# alim_MOSFET_1.net
KiCad netlist of a schematic drawn in Altium Designer
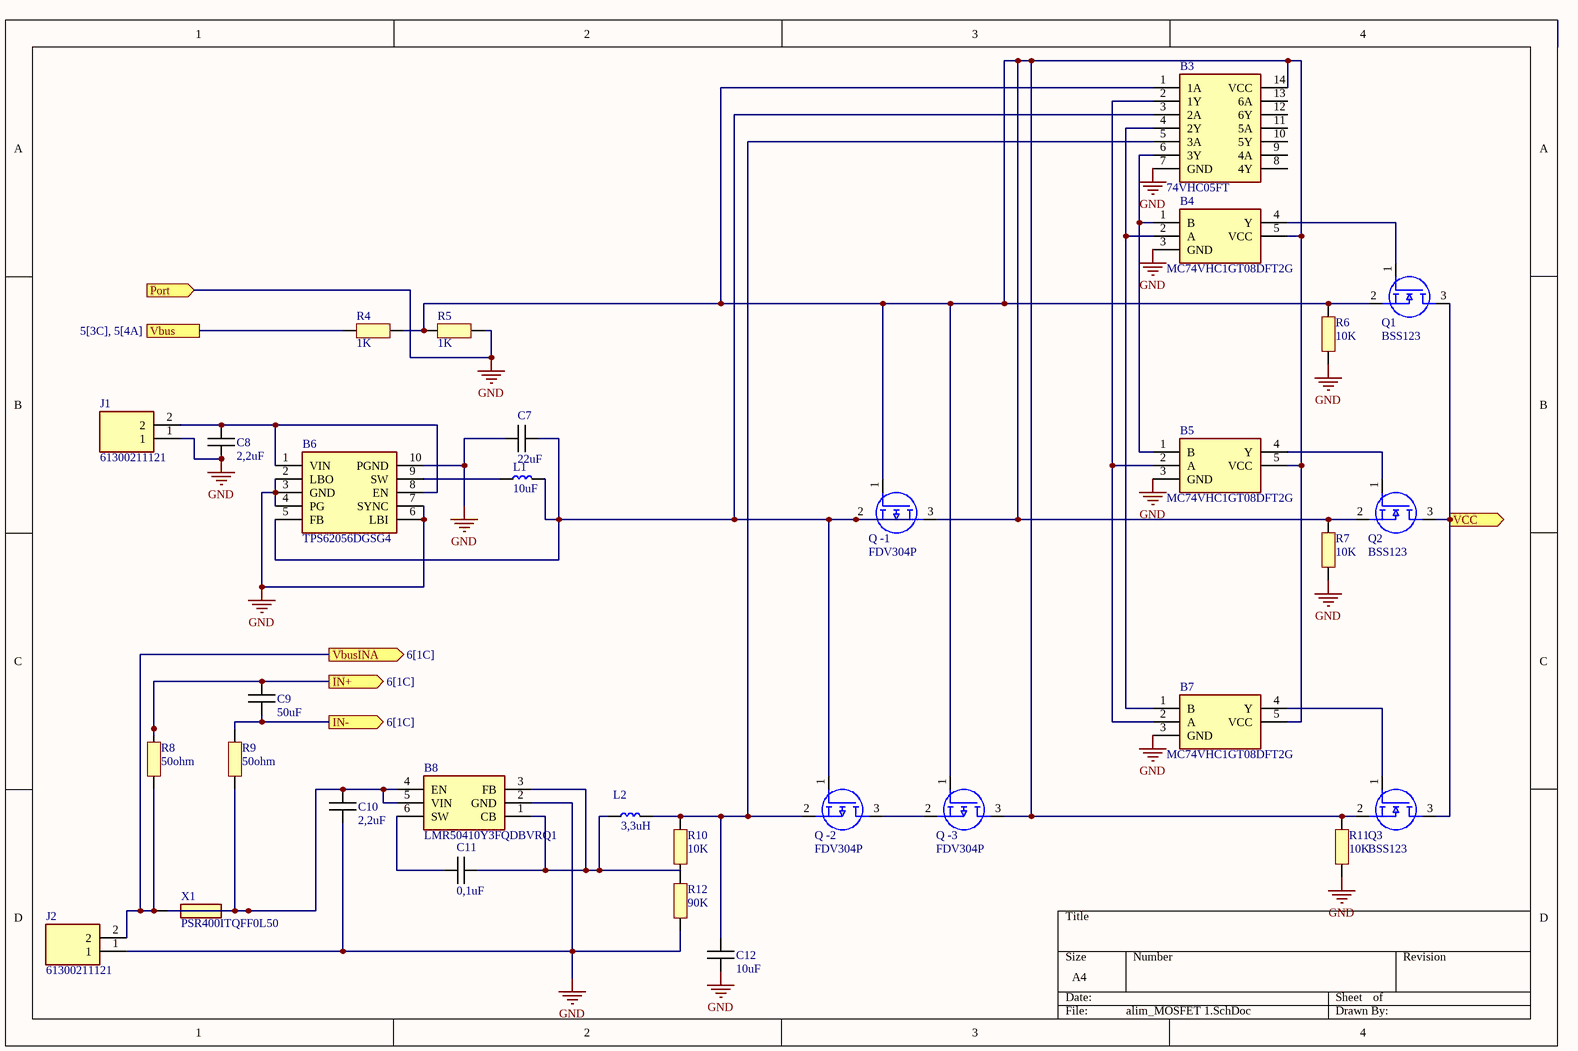
[diagram p0: alim_MOSFET 1.SchDoc]

(export (version "E")
  (design (tool "Eeschema 10.0.6"))
  (components
    (comp (ref "B3")
      (value "74VHC05FT")
      (footprint "SOP65P640X120-14N")
      (description "Logic Gates CMOS LOGIC IC INVERTER")
      (fields (field (name "MOUSER PART NUMBER") "757-74VHC05FT"))
      (libsource (lib "SCHLibrary") (part "74VHC05FT"))
    )
    (comp (ref "B4")
      (value "MC74VHC1GT08DFT2G")
      (footprint "SOT65P210X110-5N")
      (description "Single 2-Input AND Gate, TTL Level")
      (libsource (lib "SCHLibrary") (part "MC74VHC1GT08DFT2G"))
    )
    (comp (ref "B5")
      (value "MC74VHC1GT08DFT2G")
      (footprint "SOT65P210X110-5N")
      (description "Single 2-Input AND Gate, TTL Level")
      (libsource (lib "SCHLibrary") (part "MC74VHC1GT08DFT2G"))
    )
    (comp (ref "B6")
      (value "TPS62056DGSG4")
      (footprint "SOP50P490X110-10N")
      (fields (field (name "MOUSER PART NUMBER") "595-TPS62056DGSG4"))
      (libsource (lib "SCHLibrary") (part "TPS62056DGSG4"))
    )
    (comp (ref "B7")
      (value "MC74VHC1GT08DFT2G")
      (footprint "SOT65P210X110-5N")
      (description "Single 2-Input AND Gate, TTL Level")
      (libsource (lib "SCHLibrary") (part "MC74VHC1GT08DFT2G"))
    )
    (comp (ref "B8")
      (value "LMR50410Y3FQDBVRQ1")
      (footprint "SOT95P280X145-6N")
      (fields (field (name "MOUSER PART NUMBER") "595-R50410Y3FQDBVRQ1"))
      (libsource (lib "SCHLibrary") (part "LMR50410Y3FQDBVRQ1"))
    )
    (comp (ref "C7")
      (value "22uF")
      (footprint "CAPC1005X06N")
      (libsource (lib "SCHLibrary") (part "Capacitor"))
    )
    (comp (ref "C8")
      (value "2,2uF")
      (footprint "CAPC1005X06N")
      (libsource (lib "SCHLibrary") (part "Capacitor"))
    )
    (comp (ref "C9")
      (value "50uF")
      (footprint "CAPC1005X06N")
      (libsource (lib "SCHLibrary") (part "Capacitor"))
    )
    (comp (ref "C10")
      (value "2,2uF")
      (footprint "CAPC1005X06N")
      (libsource (lib "SCHLibrary") (part "Capacitor"))
    )
    (comp (ref "C11")
      (value "0,1uF")
      (footprint "CAPC1005X06N")
      (libsource (lib "SCHLibrary") (part "Capacitor"))
    )
    (comp (ref "C12")
      (value "10uF")
      (footprint "CAPC1005X06N")
      (libsource (lib "SCHLibrary") (part "Capacitor"))
    )
    (comp (ref "J1")
      (value "61300211121")
      (footprint "61300211121")
      (description "WURTH ELEKTRONIK - 61300211121 - HEADER, 2.54MM, PIN, THT, VERTICAL, 2WAY")
      (libsource (lib "SCHLibrary") (part "61300211121"))
    )
    (comp (ref "J2")
      (value "61300211121")
      (footprint "61300211121")
      (description "WURTH ELEKTRONIK - 61300211121 - HEADER, 2.54MM, PIN, THT, VERTICAL, 2WAY")
      (libsource (lib "SCHLibrary") (part "61300211121"))
    )
    (comp (ref "L1") (value "10uF") (footprint "LQPC1005X06N") (libsource (lib "SCHLibrary") (part "Bobine")))
    (comp (ref "L2")
      (value "3,3uH")
      (footprint "LQPC1005X06N")
      (libsource (lib "SCHLibrary") (part "Bobine"))
    )
    (comp (ref "Q -1")
      (value "FDV304P")
      (footprint "SOT95P251X112-3N")
      (fields (field (name "MOUSER PART NUMBER") "512-FDV304P"))
      (libsource (lib "SCHLibrary") (part "FDV304P"))
    )
    (comp (ref "Q -2")
      (value "FDV304P")
      (footprint "SOT95P251X112-3N")
      (fields (field (name "MOUSER PART NUMBER") "512-FDV304P"))
      (libsource (lib "SCHLibrary") (part "FDV304P"))
    )
    (comp (ref "Q -3")
      (value "FDV304P")
      (footprint "SOT95P251X112-3N")
      (fields (field (name "MOUSER PART NUMBER") "512-FDV304P"))
      (libsource (lib "SCHLibrary") (part "FDV304P"))
    )
    (comp (ref "Q1")
      (value "BSS123")
      (footprint "BSS123")
      (description "BSS123 N-Channel MOSFET, 170 mA, 100 V PowerTrench, 3-Pin SOT-23 ON Semiconductor")
      (libsource (lib "SCHLibrary") (part "BSS123"))
    )
    (comp (ref "Q2")
      (value "BSS123")
      (footprint "BSS123")
      (description "BSS123 N-Channel MOSFET, 170 mA, 100 V PowerTrench, 3-Pin SOT-23 ON Semiconductor")
      (libsource (lib "SCHLibrary") (part "BSS123"))
    )
    (comp (ref "Q3")
      (value "BSS123")
      (footprint "BSS123")
      (description "BSS123 N-Channel MOSFET, 170 mA, 100 V PowerTrench, 3-Pin SOT-23 ON Semiconductor")
      (libsource (lib "SCHLibrary") (part "BSS123"))
    )
    (comp (ref "R4") (value "1K") (footprint "RESC1005X06N") (libsource (lib "") (part "Resistor_1")))
    (comp (ref "R5") (value "1K") (footprint "RESC1005X06N") (libsource (lib "") (part "Resistor_1")))
    (comp (ref "R6")
      (value "10K")
      (footprint "RESC1005X06N")
      (libsource (lib "SCHLibrary") (part "Resistor"))
    )
    (comp (ref "R7")
      (value "10K")
      (footprint "RESC1005X06N")
      (libsource (lib "SCHLibrary") (part "Resistor"))
    )
    (comp (ref "R8") (value "50ohm") (footprint "RESC1005X06N") (libsource (lib "") (part "Resistor_2")))
    (comp (ref "R9") (value "50ohm") (footprint "RESC1005X06N") (libsource (lib "") (part "Resistor_2")))
    (comp (ref "R10")
      (value "10K")
      (footprint "RESC1005X06N")
      (libsource (lib "SCHLibrary") (part "Resistor"))
    )
    (comp (ref "R11")
      (value "10K")
      (footprint "RESC1005X06N")
      (libsource (lib "SCHLibrary") (part "Resistor"))
    )
    (comp (ref "R12")
      (value "90K")
      (footprint "RESC1005X06N")
      (libsource (lib "SCHLibrary") (part "Resistor"))
    )
    (comp (ref "X1")
      (value "PSR400ITQFF0L50")
      (footprint "RESC10052X200N")
      (fields (field (name "MOUSER PART NUMBER") "755-PSR400ITQFF0L50"))
      (libsource (lib "SCHLibrary") (part "PSR400ITQFF0L50"))
    )
  )
  (nets
    (net (code "1") (name "/IN+") (class "Default")
      (node (ref "C9") (pin "1") (pinfunction "1_1") (pintype "passive"))
      (node (ref "R8") (pin "2") (pinfunction "2_2") (pintype "passive"))
    )
    (net (code "2") (name "/IN-") (class "Default")
      (node (ref "C9") (pin "2") (pinfunction "2_2") (pintype "passive"))
      (node (ref "R9") (pin "2") (pinfunction "2_2") (pintype "passive"))
    )
    (net (code "3") (name "/VCC") (class "Default")
      (node (ref "Q1") (pin "3") (pinfunction "D_3") (pintype "passive"))
      (node (ref "Q2") (pin "3") (pinfunction "D_3") (pintype "passive"))
      (node (ref "Q3") (pin "3") (pinfunction "D_3") (pintype "passive"))
    )
    (net (code "4") (name "/Vbus") (class "Default")
      (node (ref "R4") (pin "1") (pinfunction "1_1") (pintype "passive"))
    )
    (net (code "5") (name "/VbusINA") (class "Default")
      (node (ref "J2") (pin "2") (pinfunction "2_2") (pintype "passive"))
      (node (ref "R8") (pin "1") (pinfunction "1_1") (pintype "passive"))
      (node (ref "X1") (pin "1") (pinfunction "1_1") (pintype "passive"))
    )
    (net (code "6") (name "GND") (class "Default")
      (node (ref "B3") (pin "7") (pinfunction "GND_7") (pintype "passive"))
      (node (ref "B4") (pin "3") (pinfunction "GND_3") (pintype "passive"))
      (node (ref "B5") (pin "3") (pinfunction "GND_3") (pintype "passive"))
      (node (ref "B6") (pin "10") (pinfunction "PGND_10") (pintype "passive"))
      (node (ref "B6") (pin "2") (pinfunction "LBO_2") (pintype "passive"))
      (node (ref "B6") (pin "3") (pinfunction "GND_3") (pintype "passive"))
      (node (ref "B6") (pin "4") (pinfunction "PG_4") (pintype "passive"))
      (node (ref "B6") (pin "6") (pinfunction "LBI_6") (pintype "passive"))
      (node (ref "B6") (pin "7") (pinfunction "SYNC_7") (pintype "passive"))
      (node (ref "B7") (pin "3") (pinfunction "GND_3") (pintype "passive"))
      (node (ref "B8") (pin "2") (pinfunction "GND_2") (pintype "passive"))
      (node (ref "C10") (pin "2") (pinfunction "2_2") (pintype "passive"))
      (node (ref "C12") (pin "2") (pinfunction "2_2") (pintype "passive"))
      (node (ref "C7") (pin "2") (pinfunction "2_2") (pintype "passive"))
      (node (ref "C8") (pin "2") (pinfunction "2_2") (pintype "passive"))
      (node (ref "J1") (pin "1") (pinfunction "1_1") (pintype "passive"))
      (node (ref "J2") (pin "1") (pinfunction "1_1") (pintype "passive"))
      (node (ref "R11") (pin "2") (pinfunction "2_2") (pintype "passive"))
      (node (ref "R12") (pin "2") (pinfunction "2_2") (pintype "passive"))
      (node (ref "R5") (pin "2") (pinfunction "2_2") (pintype "passive"))
      (node (ref "R6") (pin "2") (pinfunction "2_2") (pintype "passive"))
      (node (ref "R7") (pin "2") (pinfunction "2_2") (pintype "passive"))
    )
    (net (code "7") (name "Net-(B3-1A)") (class "Default")
      (node (ref "B3") (pin "1") (pinfunction "1A_1") (pintype "passive"))
      (node (ref "B3") (pin "14") (pinfunction "VCC_14") (pintype "passive"))
      (node (ref "B4") (pin "5") (pinfunction "VCC_5") (pintype "passive"))
      (node (ref "B5") (pin "5") (pinfunction "VCC_5") (pintype "passive"))
      (node (ref "B7") (pin "5") (pinfunction "VCC_5") (pintype "passive"))
      (node (ref "Q -1") (pin "1") (pinfunction "G_1") (pintype "passive"))
      (node (ref "Q -1") (pin "3") (pinfunction "D_3") (pintype "passive"))
      (node (ref "Q -3") (pin "1") (pinfunction "G_1") (pintype "passive"))
      (node (ref "Q -3") (pin "3") (pinfunction "D_3") (pintype "passive"))
      (node (ref "Q1") (pin "2") (pinfunction "S_2") (pintype "passive"))
      (node (ref "Q2") (pin "2") (pinfunction "S_2") (pintype "passive"))
      (node (ref "Q3") (pin "2") (pinfunction "S_2") (pintype "passive"))
      (node (ref "R11") (pin "1") (pinfunction "1_1") (pintype "passive"))
      (node (ref "R4") (pin "2") (pinfunction "2_2") (pintype "passive"))
      (node (ref "R5") (pin "1") (pinfunction "1_1") (pintype "passive"))
      (node (ref "R6") (pin "1") (pinfunction "1_1") (pintype "passive"))
      (node (ref "R7") (pin "1") (pinfunction "1_1") (pintype "passive"))
    )
    (net (code "8") (name "Net-(B3-1Y)") (class "Default")
      (node (ref "B3") (pin "2") (pinfunction "1Y_2") (pintype "passive"))
      (node (ref "B5") (pin "2") (pinfunction "A_2") (pintype "passive"))
      (node (ref "B7") (pin "2") (pinfunction "A_2") (pintype "passive"))
    )
    (net (code "9") (name "Net-(B3-2A)") (class "Default")
      (node (ref "B3") (pin "3") (pinfunction "2A_3") (pintype "passive"))
      (node (ref "B6") (pin "5") (pinfunction "FB_5") (pintype "passive"))
      (node (ref "C7") (pin "1") (pinfunction "1_1") (pintype "passive"))
      (node (ref "L1") (pin "2") (pinfunction "2_2") (pintype "passive"))
      (node (ref "Q -1") (pin "2") (pinfunction "S_2") (pintype "passive"))
      (node (ref "Q -2") (pin "1") (pinfunction "G_1") (pintype "passive"))
    )
    (net (code "10") (name "Net-(B3-2Y)") (class "Default")
      (node (ref "B3") (pin "4") (pinfunction "2Y_4") (pintype "passive"))
      (node (ref "B4") (pin "2") (pinfunction "A_2") (pintype "passive"))
      (node (ref "B7") (pin "1") (pinfunction "B_1") (pintype "passive"))
    )
    (net (code "11") (name "Net-(B3-3A)") (class "Default")
      (node (ref "B3") (pin "5") (pinfunction "3A_5") (pintype "passive"))
      (node (ref "C12") (pin "1") (pinfunction "1_1") (pintype "passive"))
      (node (ref "L2") (pin "2") (pinfunction "2_2") (pintype "passive"))
      (node (ref "Q -2") (pin "2") (pinfunction "S_2") (pintype "passive"))
      (node (ref "R10") (pin "1") (pinfunction "1_1") (pintype "passive"))
    )
    (net (code "12") (name "Net-(B3-3Y)") (class "Default")
      (node (ref "B3") (pin "6") (pinfunction "3Y_6") (pintype "passive"))
      (node (ref "B4") (pin "1") (pinfunction "B_1") (pintype "passive"))
      (node (ref "B5") (pin "1") (pinfunction "B_1") (pintype "passive"))
    )
    (net (code "13") (name "Net-(B4-Y)") (class "Default")
      (node (ref "B4") (pin "4") (pinfunction "Y_4") (pintype "passive"))
      (node (ref "Q1") (pin "1") (pinfunction "G_1") (pintype "passive"))
    )
    (net (code "14") (name "Net-(B5-Y)") (class "Default")
      (node (ref "B5") (pin "4") (pinfunction "Y_4") (pintype "passive"))
      (node (ref "Q2") (pin "1") (pinfunction "G_1") (pintype "passive"))
    )
    (net (code "15") (name "Net-(B6-EN)") (class "Default")
      (node (ref "B6") (pin "1") (pinfunction "VIN_1") (pintype "passive"))
      (node (ref "B6") (pin "8") (pinfunction "EN_8") (pintype "passive"))
      (node (ref "C8") (pin "1") (pinfunction "1_1") (pintype "passive"))
      (node (ref "J1") (pin "2") (pinfunction "2_2") (pintype "passive"))
    )
    (net (code "16") (name "Net-(B6-SW)") (class "Default")
      (node (ref "B6") (pin "9") (pinfunction "SW_9") (pintype "passive"))
      (node (ref "L1") (pin "1") (pinfunction "1_1") (pintype "passive"))
    )
    (net (code "17") (name "Net-(B7-Y)") (class "Default")
      (node (ref "B7") (pin "4") (pinfunction "Y_4") (pintype "passive"))
      (node (ref "Q3") (pin "1") (pinfunction "G_1") (pintype "passive"))
    )
    (net (code "18") (name "Net-(B8-CB)") (class "Default")
      (node (ref "B8") (pin "1") (pinfunction "CB_1") (pintype "passive"))
      (node (ref "B8") (pin "3") (pinfunction "FB_3") (pintype "passive"))
      (node (ref "C11") (pin "1") (pinfunction "1_1") (pintype "passive"))
      (node (ref "L2") (pin "1") (pinfunction "1_1") (pintype "passive"))
      (node (ref "R12") (pin "1") (pinfunction "1_1") (pintype "passive"))
    )
    (net (code "19") (name "Net-(B8-EN)") (class "Default")
      (node (ref "B8") (pin "4") (pinfunction "EN_4") (pintype "passive"))
      (node (ref "B8") (pin "5") (pinfunction "VIN_5") (pintype "passive"))
      (node (ref "C10") (pin "1") (pinfunction "1_1") (pintype "passive"))
      (node (ref "R9") (pin "1") (pinfunction "1_1") (pintype "passive"))
      (node (ref "X1") (pin "2") (pinfunction "2_2") (pintype "passive"))
    )
    (net (code "20") (name "Net-(B8-SW)") (class "Default")
      (node (ref "B8") (pin "6") (pinfunction "SW_6") (pintype "passive"))
      (node (ref "C11") (pin "2") (pinfunction "2_2") (pintype "passive"))
    )
    (net (code "21") (name "Net-(Q -2-D)") (class "Default")
      (node (ref "Q -2") (pin "3") (pinfunction "D_3") (pintype "passive"))
      (node (ref "Q -3") (pin "2") (pinfunction "S_2") (pintype "passive"))
    )
    (net (code "22") (name "unconnected-(B3-4A-Pad9)") (class "Default")
      (node (ref "B3") (pin "9") (pinfunction "4A_9") (pintype "passive"))
    )
    (net (code "23") (name "unconnected-(B3-4Y-Pad8)") (class "Default")
      (node (ref "B3") (pin "8") (pinfunction "4Y_8") (pintype "passive"))
    )
    (net (code "24") (name "unconnected-(B3-5A-Pad11)") (class "Default")
      (node (ref "B3") (pin "11") (pinfunction "5A_11") (pintype "passive"))
    )
    (net (code "25") (name "unconnected-(B3-5Y-Pad10)") (class "Default")
      (node (ref "B3") (pin "10") (pinfunction "5Y_10") (pintype "passive"))
    )
    (net (code "26") (name "unconnected-(B3-6A-Pad13)") (class "Default")
      (node (ref "B3") (pin "13") (pinfunction "6A_13") (pintype "passive"))
    )
    (net (code "27") (name "unconnected-(B3-6Y-Pad12)") (class "Default")
      (node (ref "B3") (pin "12") (pinfunction "6Y_12") (pintype "passive"))
    )
    (net (code "28") (name "unconnected-(R10-Pad2)") (class "Default")
      (node (ref "R10") (pin "2") (pinfunction "2_2") (pintype "passive"))
    )
  )
)
